# bio_dnt_power.net
KiCad netlist of a schematic drawn in Altium Designer
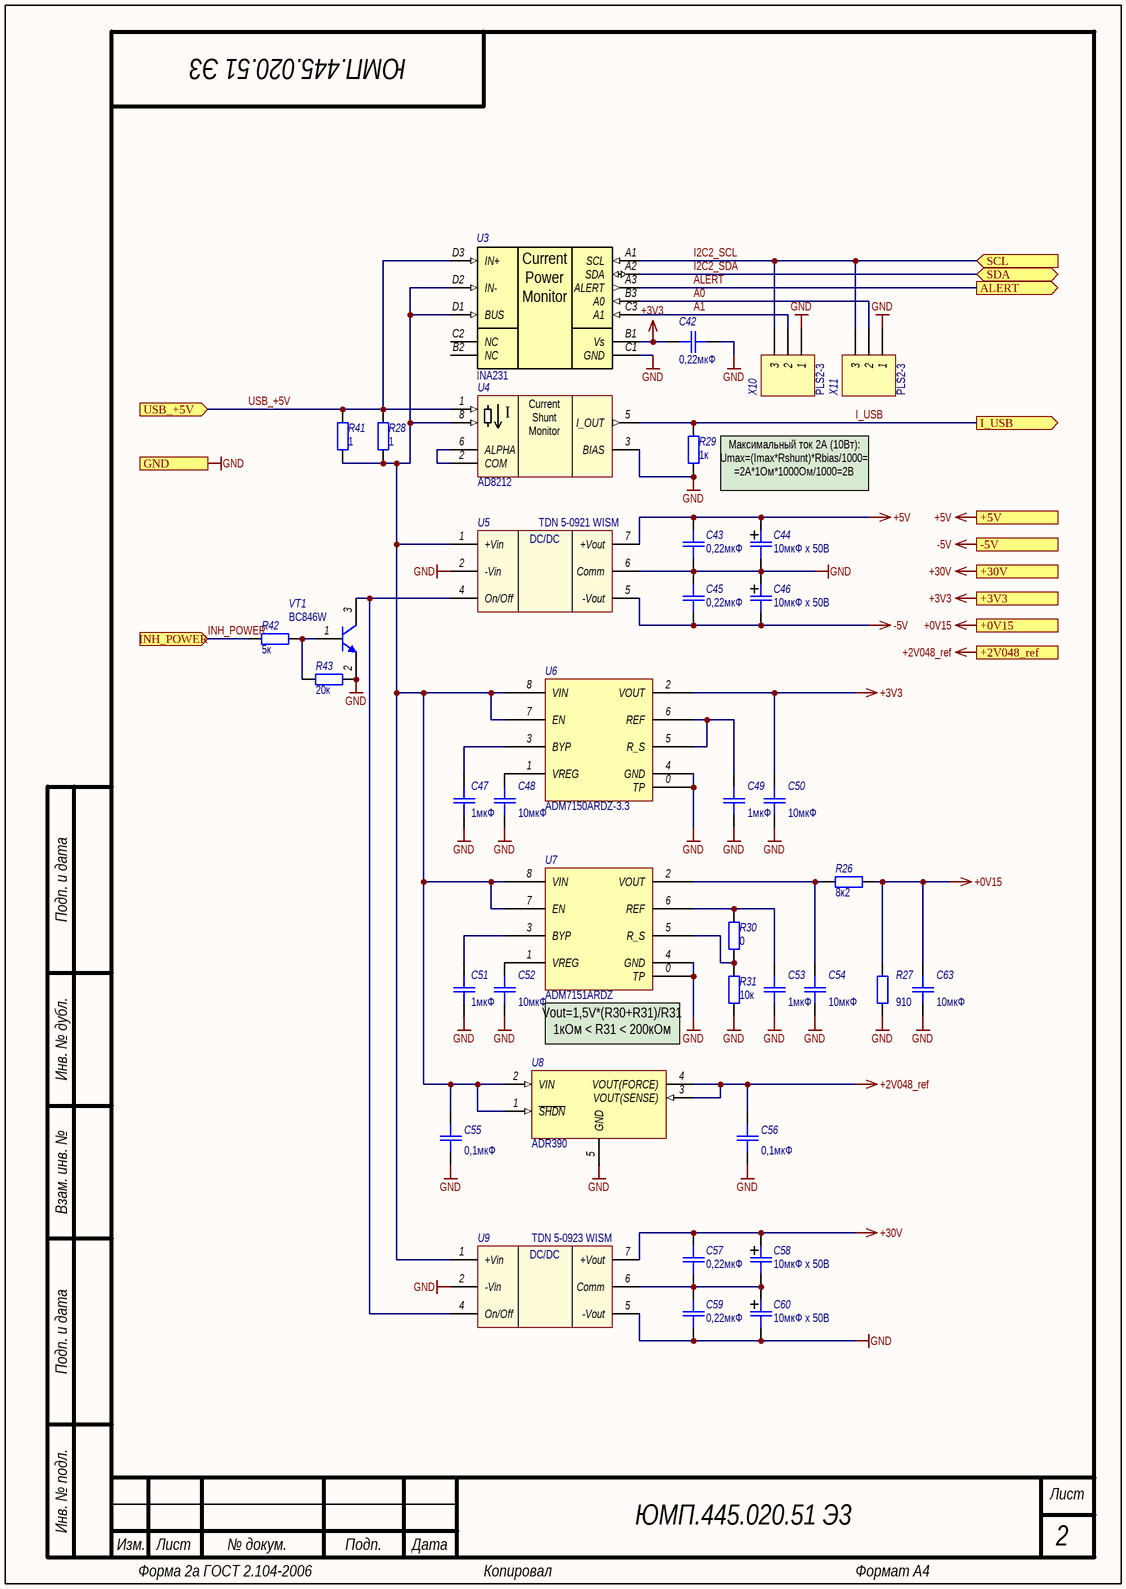
[diagram p0: bio_dnt_power.SchDoc]

(export (version "E")
  (design (tool "Eeschema 10.0.6"))
  (components
    (comp (ref "C42")
      (value "0,22мкФ")
      (footprint "CR-0805")
      (description "Конденсатор для поверхностного монтажа")
      (libsource (lib "my_passive") (part "C_smd"))
    )
    (comp (ref "C43")
      (value "0,22мкФ")
      (footprint "CR-0805")
      (description "Конденсатор для поверхностного монтажа")
      (libsource (lib "my_passive") (part "C_smd"))
    )
    (comp (ref "C44")
      (value "10мкФ х 50В")
      (footprint "C_SMD_size_C")
      (description "Поляризованный конеднсатор для поверхностного монтажа")
      (libsource (lib "my_passive") (part "C_pol_smd"))
    )
    (comp (ref "C45")
      (value "0,22мкФ")
      (footprint "CR-0805")
      (description "Конденсатор для поверхностного монтажа")
      (libsource (lib "my_passive") (part "C_smd"))
    )
    (comp (ref "C46")
      (value "10мкФ х 50В")
      (footprint "C_SMD_size_C")
      (description "Поляризованный конеднсатор для поверхностного монтажа")
      (libsource (lib "my_passive") (part "C_pol_smd"))
    )
    (comp (ref "C47")
      (value "1мкФ")
      (footprint "CR-0805")
      (description "Конденсатор для поверхностного монтажа")
      (libsource (lib "my_passive") (part "C_smd"))
    )
    (comp (ref "C48")
      (value "10мкФ")
      (footprint "CR-0805")
      (description "Конденсатор для поверхностного монтажа")
      (libsource (lib "my_passive") (part "C_smd"))
    )
    (comp (ref "C49")
      (value "1мкФ")
      (footprint "CR-0805")
      (description "Конденсатор для поверхностного монтажа")
      (libsource (lib "my_passive") (part "C_smd"))
    )
    (comp (ref "C50")
      (value "10мкФ")
      (footprint "CR-0805")
      (description "Конденсатор для поверхностного монтажа")
      (libsource (lib "my_passive") (part "C_smd"))
    )
    (comp (ref "C51")
      (value "1мкФ")
      (footprint "CR-0805")
      (description "Конденсатор для поверхностного монтажа")
      (libsource (lib "my_passive") (part "C_smd"))
    )
    (comp (ref "C52")
      (value "10мкФ")
      (footprint "CR-0805")
      (description "Конденсатор для поверхностного монтажа")
      (libsource (lib "my_passive") (part "C_smd"))
    )
    (comp (ref "C53")
      (value "1мкФ")
      (footprint "CR-0805")
      (description "Конденсатор для поверхностного монтажа")
      (libsource (lib "my_passive") (part "C_smd"))
    )
    (comp (ref "C54")
      (value "10мкФ")
      (footprint "CR-0805")
      (description "Конденсатор для поверхностного монтажа")
      (libsource (lib "my_passive") (part "C_smd"))
    )
    (comp (ref "C55")
      (value "0,1мкФ")
      (footprint "CR-0805")
      (description "Конденсатор для поверхностного монтажа")
      (libsource (lib "my_passive") (part "C_smd"))
    )
    (comp (ref "C56")
      (value "0,1мкФ")
      (footprint "CR-0805")
      (description "Конденсатор для поверхностного монтажа")
      (libsource (lib "my_passive") (part "C_smd"))
    )
    (comp (ref "C57")
      (value "0,22мкФ")
      (footprint "CR-0805")
      (description "Конденсатор для поверхностного монтажа")
      (libsource (lib "my_passive") (part "C_smd"))
    )
    (comp (ref "C58")
      (value "10мкФ х 50В")
      (footprint "C_SMD_size_C")
      (description "Поляризованный конеднсатор для поверхностного монтажа")
      (libsource (lib "my_passive") (part "C_pol_smd"))
    )
    (comp (ref "C59")
      (value "0,22мкФ")
      (footprint "CR-0805")
      (description "Конденсатор для поверхностного монтажа")
      (libsource (lib "my_passive") (part "C_smd"))
    )
    (comp (ref "C60")
      (value "10мкФ х 50В")
      (footprint "C_SMD_size_C")
      (description "Поляризованный конеднсатор для поверхностного монтажа")
      (libsource (lib "my_passive") (part "C_pol_smd"))
    )
    (comp (ref "C63")
      (value "10мкФ")
      (footprint "CR-0805")
      (description "Конденсатор для поверхностного монтажа")
      (libsource (lib "my_passive") (part "C_smd"))
    )
    (comp (ref "R26")
      (value "8к2")
      (footprint "CR-0805")
      (description "Резистор для поверхностного монтажа")
      (libsource (lib "") (part "R_smd_1"))
    )
    (comp (ref "R27")
      (value "910")
      (footprint "CR-0805")
      (description "Резистор для поверхностного монтажа")
      (libsource (lib "") (part "R_smd_2"))
    )
    (comp (ref "R28")
      (value "1")
      (footprint "CR-0805")
      (description "Резистор для поверхностного монтажа")
      (libsource (lib "my_passive") (part "R_smd"))
    )
    (comp (ref "R29")
      (value "1к")
      (footprint "CR-0805")
      (description "Резистор для поверхностного монтажа")
      (libsource (lib "my_passive") (part "R_smd"))
    )
    (comp (ref "R30")
      (value "0")
      (footprint "CR-0805")
      (description "Резистор для поверхностного монтажа")
      (libsource (lib "my_passive") (part "R_smd"))
    )
    (comp (ref "R31")
      (value "10к")
      (footprint "CR-0805")
      (description "Резистор для поверхностного монтажа")
      (libsource (lib "my_passive") (part "R_smd"))
    )
    (comp (ref "R41")
      (value "1")
      (footprint "CR-0805")
      (description "Резистор для поверхностного монтажа")
      (libsource (lib "my_passive") (part "R_smd"))
    )
    (comp (ref "R42")
      (value "5к")
      (footprint "CR-0805")
      (description "Резистор для поверхностного монтажа")
      (libsource (lib "") (part "R_smd_3"))
    )
    (comp (ref "R43")
      (value "20к")
      (footprint "CR-0805")
      (description "Резистор для поверхностного монтажа")
      (libsource (lib "") (part "R_smd_3"))
    )
    (comp (ref "U3")
      (value "INA231")
      (footprint "DSBGA-12")
      (description "High- or Low-Side Measurement, Bidirectional Current and Power Monitor With 1.8-V I2C Interface")
      (fields (field (name "НАИМЕНОВАНИЕ") "INA231"))
      (libsource (lib "my_power") (part "INA231"))
    )
    (comp (ref "U4")
      (value "AD8212")
      (footprint "MSOP-8")
      (description "Current Shunt Monitor")
      (fields (field (name "НАИМЕНОВАНИЕ") "AD8212"))
      (libsource (lib "my_power") (part "AD8212"))
    )
    (comp (ref "U5")
      (value "TDN 5 WISM")
      (footprint "TDN 5 WISM")
      (description "DC/DC converter")
      (fields (field (name "НАИМЕНОВАНИЕ") "TDN 5-0921 WISM"))
      (libsource (lib "my_power") (part "TDN 5 WISM"))
    )
    (comp (ref "U6")
      (value "ADM7150")
      (footprint "SOIC-8 + Exposed Pad")
      (description "800 mA Ultralow Noise, High PSRR, RF Linear Regulator")
      (fields (field (name "НАИМЕНОВАНИЕ") "ADM7150ARDZ-3.3"))
      (libsource (lib "my_integrated_circuit") (part "ADM7150"))
    )
    (comp (ref "U7")
      (value "ADM7151")
      (footprint "SOIC-8 + Exposed Pad")
      (description "800 mA Ultralow Noise, High PSRR, Adjustable, RF Linear Regulator")
      (fields (field (name "НАИМЕНОВАНИЕ") "ADM7151ARDZ"))
      (libsource (lib "my_integrated_circuit") (part "ADM7151"))
    )
    (comp (ref "U8")
      (value "ADR39х")
      (footprint "TSOT-5")
      (fields
        (field (name "MANUFACTURER") "Analog Devices")
        (field (name "PARTNUMBER") "ADR391BUJZ-REEL7")
        (field (name "НАИМЕНОВАНИЕ") "ADR390")
      )
      (libsource (lib "my_power") (part "ADR39x"))
    )
    (comp (ref "U9")
      (value "TDN 5 WISM")
      (footprint "TDN 5 WISM")
      (description "DC/DC converter")
      (fields (field (name "НАИМЕНОВАНИЕ") "TDN 5-0923 WISM"))
      (libsource (lib "my_power") (part "TDN 5 WISM"))
    )
    (comp (ref "VT1")
      (value "BC846BWT1")
      (footprint "SOT-23")
      (description "General Purpose Transistor, NPN Silicon, 3-Pin SC70, Tape and Reel")
      (fields (field (name "MANUFACTURER") "On Semiconductor") (field (name "НАИМЕНОВАНИЕ") "BC846W"))
      (libsource (lib "my_semicond") (part "BC846BWT1"))
    )
    (comp (ref "X10")
      (value "MHDR1X3")
      (footprint "SJMP-3")
      (description "Header, 3-Pin")
      (fields (field (name "НАИМЕНОВАНИЕ") "PLS2-3") (field (name "PUBLISHER") "Altium Limited"))
      (libsource (lib "my_connector") (part "MHDR1X3"))
    )
    (comp (ref "X11")
      (value "MHDR1X3")
      (footprint "SJMP-3")
      (description "Header, 3-Pin")
      (fields (field (name "НАИМЕНОВАНИЕ") "PLS2-3") (field (name "PUBLISHER") "Altium Limited"))
      (libsource (lib "my_connector") (part "MHDR1X3"))
    )
  )
  (nets
    (net (code "1") (name "+0V15") (class "Default")
      (node (ref "C63") (pin "2") (pinfunction "2_2") (pintype "passive"))
      (node (ref "R26") (pin "2") (pinfunction "2_2") (pintype "passive"))
      (node (ref "R27") (pin "2") (pinfunction "2_2") (pintype "passive"))
    )
    (net (code "2") (name "+2V048_ref") (class "Default")
      (node (ref "C56") (pin "2") (pinfunction "2_2") (pintype "passive"))
      (node (ref "U8") (pin "3") (pinfunction "VOUT(SENSE)_3") (pintype "input"))
      (node (ref "U8") (pin "4") (pinfunction "VOUT(FORCE)_4") (pintype "tri_state"))
    )
    (net (code "3") (name "+3V3") (class "Default")
      (node (ref "C42") (pin "2") (pinfunction "2_2") (pintype "passive"))
      (node (ref "C50") (pin "2") (pinfunction "2_2") (pintype "passive"))
      (node (ref "U3") (pin "B1") (pinfunction "Vs_B1") (pintype "power_in"))
      (node (ref "U6") (pin "2") (pinfunction "VOUT_2") (pintype "passive"))
    )
    (net (code "4") (name "+5V") (class "Default")
      (node (ref "C43") (pin "2") (pinfunction "2_2") (pintype "passive"))
      (node (ref "C44") (pin "1") (pinfunction "1_1") (pintype "passive"))
      (node (ref "U5") (pin "7") (pinfunction "+Vout_7") (pintype "open_collector"))
    )
    (net (code "5") (name "+30V") (class "Default")
      (node (ref "C57") (pin "2") (pinfunction "2_2") (pintype "passive"))
      (node (ref "C58") (pin "1") (pinfunction "1_1") (pintype "passive"))
      (node (ref "U9") (pin "7") (pinfunction "+Vout_7") (pintype "open_collector"))
    )
    (net (code "6") (name "-5V") (class "Default")
      (node (ref "C45") (pin "1") (pinfunction "1_1") (pintype "passive"))
      (node (ref "C46") (pin "2") (pinfunction "2_2") (pintype "passive"))
      (node (ref "U5") (pin "5") (pinfunction "-Vout_5") (pintype "open_collector"))
    )
    (net (code "7") (name "/A0") (class "Default")
      (node (ref "U3") (pin "B3") (pinfunction "A0_B3") (pintype "input"))
      (node (ref "X11") (pin "2") (pinfunction "2_2") (pintype "passive"))
    )
    (net (code "8") (name "/A1") (class "Default")
      (node (ref "U3") (pin "C3") (pinfunction "A1_C3") (pintype "input"))
      (node (ref "X10") (pin "2") (pinfunction "2_2") (pintype "passive"))
    )
    (net (code "9") (name "/ALERT") (class "Default")
      (node (ref "U3") (pin "A3") (pinfunction "ALERT_A3") (pintype "output"))
    )
    (net (code "10") (name "/I2C2_SCL") (class "Default")
      (node (ref "U3") (pin "A1") (pinfunction "SCL_A1") (pintype "input"))
      (node (ref "X10") (pin "3") (pinfunction "3_3") (pintype "passive"))
      (node (ref "X11") (pin "3") (pinfunction "3_3") (pintype "passive"))
    )
    (net (code "11") (name "/I2C2_SDA") (class "Default")
      (node (ref "U3") (pin "A2") (pinfunction "SDA_A2") (pintype "bidirectional"))
    )
    (net (code "12") (name "/INH_POWER") (class "Default")
      (node (ref "R42") (pin "2") (pinfunction "2_2") (pintype "passive"))
    )
    (net (code "13") (name "/I_USB") (class "Default")
      (node (ref "R29") (pin "1") (pinfunction "1_1") (pintype "passive"))
      (node (ref "U4") (pin "5") (pinfunction "I_OUT_5") (pintype "output"))
    )
    (net (code "14") (name "/USB_+5V") (class "Default")
      (node (ref "R28") (pin "1") (pinfunction "1_1") (pintype "passive"))
      (node (ref "R41") (pin "1") (pinfunction "1_1") (pintype "passive"))
      (node (ref "U3") (pin "D3") (pinfunction "IN+_D3") (pintype "input"))
      (node (ref "U4") (pin "1") (pinfunction "V+_1") (pintype "input"))
    )
    (net (code "15") (name "GND") (class "Default")
      (node (ref "C42") (pin "1") (pinfunction "1_1") (pintype "passive"))
      (node (ref "C43") (pin "1") (pinfunction "1_1") (pintype "passive"))
      (node (ref "C44") (pin "2") (pinfunction "2_2") (pintype "passive"))
      (node (ref "C45") (pin "2") (pinfunction "2_2") (pintype "passive"))
      (node (ref "C46") (pin "1") (pinfunction "1_1") (pintype "passive"))
      (node (ref "C47") (pin "1") (pinfunction "1_1") (pintype "passive"))
      (node (ref "C48") (pin "1") (pinfunction "1_1") (pintype "passive"))
      (node (ref "C49") (pin "1") (pinfunction "1_1") (pintype "passive"))
      (node (ref "C50") (pin "1") (pinfunction "1_1") (pintype "passive"))
      (node (ref "C51") (pin "1") (pinfunction "1_1") (pintype "passive"))
      (node (ref "C52") (pin "1") (pinfunction "1_1") (pintype "passive"))
      (node (ref "C53") (pin "1") (pinfunction "1_1") (pintype "passive"))
      (node (ref "C54") (pin "1") (pinfunction "1_1") (pintype "passive"))
      (node (ref "C55") (pin "1") (pinfunction "1_1") (pintype "passive"))
      (node (ref "C56") (pin "1") (pinfunction "1_1") (pintype "passive"))
      (node (ref "C59") (pin "1") (pinfunction "1_1") (pintype "passive"))
      (node (ref "C60") (pin "2") (pinfunction "2_2") (pintype "passive"))
      (node (ref "C63") (pin "1") (pinfunction "1_1") (pintype "passive"))
      (node (ref "R27") (pin "1") (pinfunction "1_1") (pintype "passive"))
      (node (ref "R29") (pin "2") (pinfunction "2_2") (pintype "passive"))
      (node (ref "R31") (pin "2") (pinfunction "2_2") (pintype "passive"))
      (node (ref "R43") (pin "1") (pinfunction "1_1") (pintype "passive"))
      (node (ref "U3") (pin "C1") (pinfunction "GND_C1") (pintype "power_in"))
      (node (ref "U4") (pin "3") (pinfunction "BIAS_3") (pintype "open_collector"))
      (node (ref "U5") (pin "2") (pinfunction "-Vin_2") (pintype "open_collector"))
      (node (ref "U5") (pin "6") (pinfunction "Comm_6") (pintype "open_collector"))
      (node (ref "U6") (pin "0") (pinfunction "TP_0") (pintype "passive"))
      (node (ref "U6") (pin "4") (pinfunction "GND_4") (pintype "passive"))
      (node (ref "U7") (pin "0") (pinfunction "TP_0") (pintype "passive"))
      (node (ref "U7") (pin "4") (pinfunction "GND_4") (pintype "passive"))
      (node (ref "U8") (pin "5") (pinfunction "GND_5") (pintype "power_in"))
      (node (ref "U9") (pin "2") (pinfunction "-Vin_2") (pintype "open_collector"))
      (node (ref "U9") (pin "5") (pinfunction "-Vout_5") (pintype "open_collector"))
      (node (ref "VT1") (pin "2") (pinfunction "E_2") (pintype "passive"))
      (node (ref "X10") (pin "1") (pinfunction "1_1") (pintype "passive"))
      (node (ref "X11") (pin "1") (pinfunction "1_1") (pintype "passive"))
    )
    (net (code "16") (name "Net-(U3-BUS)") (class "Default")
      (node (ref "C55") (pin "2") (pinfunction "2_2") (pintype "passive"))
      (node (ref "R28") (pin "2") (pinfunction "2_2") (pintype "passive"))
      (node (ref "R41") (pin "2") (pinfunction "2_2") (pintype "passive"))
      (node (ref "U3") (pin "D1") (pinfunction "BUS_D1") (pintype "input"))
      (node (ref "U3") (pin "D2") (pinfunction "IN-_D2") (pintype "input"))
      (node (ref "U4") (pin "8") (pinfunction "V_SENSE_8") (pintype "input"))
      (node (ref "U5") (pin "1") (pinfunction "+Vin_1") (pintype "open_collector"))
      (node (ref "U6") (pin "7") (pinfunction "EN_7") (pintype "passive"))
      (node (ref "U6") (pin "8") (pinfunction "VIN_8") (pintype "passive"))
      (node (ref "U7") (pin "7") (pinfunction "EN_7") (pintype "passive"))
      (node (ref "U7") (pin "8") (pinfunction "VIN_8") (pintype "passive"))
      (node (ref "U8") (pin "1") (pinfunction "~{SHDN}_1") (pintype "input"))
      (node (ref "U8") (pin "2") (pinfunction "VIN_2") (pintype "input"))
      (node (ref "U9") (pin "1") (pinfunction "+Vin_1") (pintype "open_collector"))
    )
    (net (code "17") (name "Net-(U4-ALPHA)") (class "Default")
      (node (ref "U4") (pin "2") (pinfunction "COM_2") (pintype "open_collector"))
      (node (ref "U4") (pin "6") (pinfunction "ALPHA_6") (pintype "open_collector"))
    )
    (net (code "18") (name "Net-(U5-On{slash}Off)") (class "Default")
      (node (ref "U5") (pin "4") (pinfunction "On/Off_4") (pintype "open_collector"))
      (node (ref "U9") (pin "4") (pinfunction "On/Off_4") (pintype "open_collector"))
      (node (ref "VT1") (pin "3") (pinfunction "C_3") (pintype "passive"))
    )
    (net (code "19") (name "Net-(U6-BYP)") (class "Default")
      (node (ref "C47") (pin "2") (pinfunction "2_2") (pintype "passive"))
      (node (ref "U6") (pin "3") (pinfunction "BYP_3") (pintype "passive"))
    )
    (net (code "20") (name "Net-(U6-REF)") (class "Default")
      (node (ref "C49") (pin "2") (pinfunction "2_2") (pintype "passive"))
      (node (ref "U6") (pin "5") (pinfunction "R_S_5") (pintype "passive"))
      (node (ref "U6") (pin "6") (pinfunction "REF_6") (pintype "passive"))
    )
    (net (code "21") (name "Net-(U6-VREG)") (class "Default")
      (node (ref "C48") (pin "2") (pinfunction "2_2") (pintype "passive"))
      (node (ref "U6") (pin "1") (pinfunction "VREG_1") (pintype "passive"))
    )
    (net (code "22") (name "Net-(U7-BYP)") (class "Default")
      (node (ref "C51") (pin "2") (pinfunction "2_2") (pintype "passive"))
      (node (ref "U7") (pin "3") (pinfunction "BYP_3") (pintype "passive"))
    )
    (net (code "23") (name "Net-(U7-REF)") (class "Default")
      (node (ref "C53") (pin "2") (pinfunction "2_2") (pintype "passive"))
      (node (ref "R30") (pin "1") (pinfunction "1_1") (pintype "passive"))
      (node (ref "U7") (pin "6") (pinfunction "REF_6") (pintype "passive"))
    )
    (net (code "24") (name "Net-(U7-R_S)") (class "Default")
      (node (ref "R30") (pin "2") (pinfunction "2_2") (pintype "passive"))
      (node (ref "R31") (pin "1") (pinfunction "1_1") (pintype "passive"))
      (node (ref "U7") (pin "5") (pinfunction "R_S_5") (pintype "passive"))
    )
    (net (code "25") (name "Net-(U7-VOUT)") (class "Default")
      (node (ref "C54") (pin "2") (pinfunction "2_2") (pintype "passive"))
      (node (ref "R26") (pin "1") (pinfunction "1_1") (pintype "passive"))
      (node (ref "U7") (pin "2") (pinfunction "VOUT_2") (pintype "passive"))
    )
    (net (code "26") (name "Net-(U7-VREG)") (class "Default")
      (node (ref "C52") (pin "2") (pinfunction "2_2") (pintype "passive"))
      (node (ref "U7") (pin "1") (pinfunction "VREG_1") (pintype "passive"))
    )
    (net (code "27") (name "Net-(U9-Comm)") (class "Default")
      (node (ref "C57") (pin "1") (pinfunction "1_1") (pintype "passive"))
      (node (ref "C58") (pin "2") (pinfunction "2_2") (pintype "passive"))
      (node (ref "C59") (pin "2") (pinfunction "2_2") (pintype "passive"))
      (node (ref "C60") (pin "1") (pinfunction "1_1") (pintype "passive"))
      (node (ref "U9") (pin "6") (pinfunction "Comm_6") (pintype "open_collector"))
    )
    (net (code "28") (name "Net-(VT1-B)") (class "Default")
      (node (ref "R42") (pin "1") (pinfunction "1_1") (pintype "passive"))
      (node (ref "R43") (pin "2") (pinfunction "2_2") (pintype "passive"))
      (node (ref "VT1") (pin "1") (pinfunction "B_1") (pintype "passive"))
    )
    (net (code "29") (name "unconnected-(U3-NC-PadB2)") (class "Default")
      (node (ref "U3") (pin "B2") (pinfunction "NC_B2") (pintype "tri_state"))
    )
    (net (code "30") (name "unconnected-(U3-NC-PadC2)") (class "Default")
      (node (ref "U3") (pin "C2") (pinfunction "NC_C2") (pintype "tri_state"))
    )
  )
)
